# power_supply.net
KiCad netlist of a schematic drawn in Altium Designer
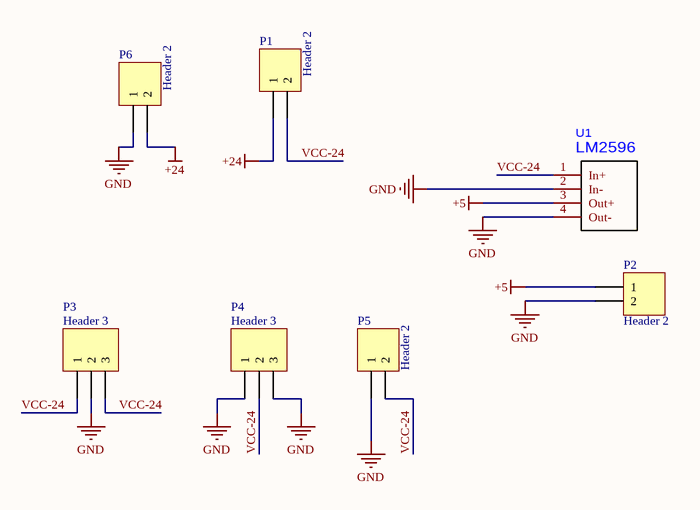
[diagram p0: power_supply.SchDoc]

(export (version "E")
  (design (tool "Eeschema 10.0.6"))
  (components
    (comp (ref "P1")
      (value "Header 2")
      (footprint "2PIN-5.08A")
      (description "Header, 2-Pin")
      (fields (field (name "PUBLISHER") "Altium Limited"))
      (libsource (lib "zy lib") (part "二口插座"))
    )
    (comp (ref "P2")
      (value "Header 2")
      (footprint "2PIN-5.08A")
      (description "Header, 2-Pin")
      (fields (field (name "PUBLISHER") "Altium Limited"))
      (libsource (lib "") (part "二口插座_1"))
    )
    (comp (ref "P3")
      (value "Header 3")
      (footprint "3PIN-5.08A")
      (description "Header, 3-Pin")
      (fields (field (name "PUBLISHER") "Altium Limited"))
      (libsource (lib "zy lib") (part "三口插座"))
    )
    (comp (ref "P4")
      (value "Header 3")
      (footprint "3PIN-5.08A")
      (description "Header, 3-Pin")
      (fields (field (name "PUBLISHER") "Altium Limited"))
      (libsource (lib "zy lib") (part "三口插座"))
    )
    (comp (ref "P5")
      (value "Header 2")
      (footprint "2PIN-5.08A")
      (description "Header, 2-Pin")
      (fields (field (name "PUBLISHER") "Altium Limited"))
      (libsource (lib "zy lib") (part "二口插座"))
    )
    (comp (ref "P6")
      (value "Header 2")
      (footprint "2PIN-5.08A")
      (description "Header, 2-Pin")
      (fields (field (name "PUBLISHER") "Altium Limited"))
      (libsource (lib "zy lib") (part "二口插座"))
    )
    (comp (ref "U1")
      (value "~")
      (footprint "LM2596")
      (libsource (lib "altium-import") (part "root_0_LM2596模块-29AH_"))
    )
  )
  (nets
    (net (code "1") (name "+5") (class "Default")
      (node (ref "P2") (pin "1") (pinfunction "1_1") (pintype "passive"))
      (node (ref "U1") (pin "3") (pinfunction "Out+_3") (pintype "passive"))
    )
    (net (code "2") (name "+24") (class "Default")
      (node (ref "P1") (pin "1") (pinfunction "1_1") (pintype "passive"))
      (node (ref "P6") (pin "2") (pinfunction "2_2") (pintype "passive"))
    )
    (net (code "3") (name "/VCC-24") (class "Default")
      (node (ref "P1") (pin "2") (pinfunction "2_2") (pintype "passive"))
      (node (ref "P3") (pin "1") (pinfunction "1_1") (pintype "passive"))
      (node (ref "P3") (pin "3") (pinfunction "3_3") (pintype "passive"))
      (node (ref "P4") (pin "2") (pinfunction "2_2") (pintype "passive"))
      (node (ref "P5") (pin "2") (pinfunction "2_2") (pintype "passive"))
      (node (ref "U1") (pin "1") (pinfunction "In+_1") (pintype "passive"))
    )
    (net (code "4") (name "GND") (class "Default")
      (node (ref "P2") (pin "2") (pinfunction "2_2") (pintype "passive"))
      (node (ref "P3") (pin "2") (pinfunction "2_2") (pintype "passive"))
      (node (ref "P4") (pin "1") (pinfunction "1_1") (pintype "passive"))
      (node (ref "P4") (pin "3") (pinfunction "3_3") (pintype "passive"))
      (node (ref "P5") (pin "1") (pinfunction "1_1") (pintype "passive"))
      (node (ref "P6") (pin "1") (pinfunction "1_1") (pintype "passive"))
      (node (ref "U1") (pin "2") (pinfunction "In-_2") (pintype "passive"))
      (node (ref "U1") (pin "4") (pinfunction "Out-_4") (pintype "passive"))
    )
  )
)
